# power_supply.net
KiCad netlist of a schematic drawn in EAGLE
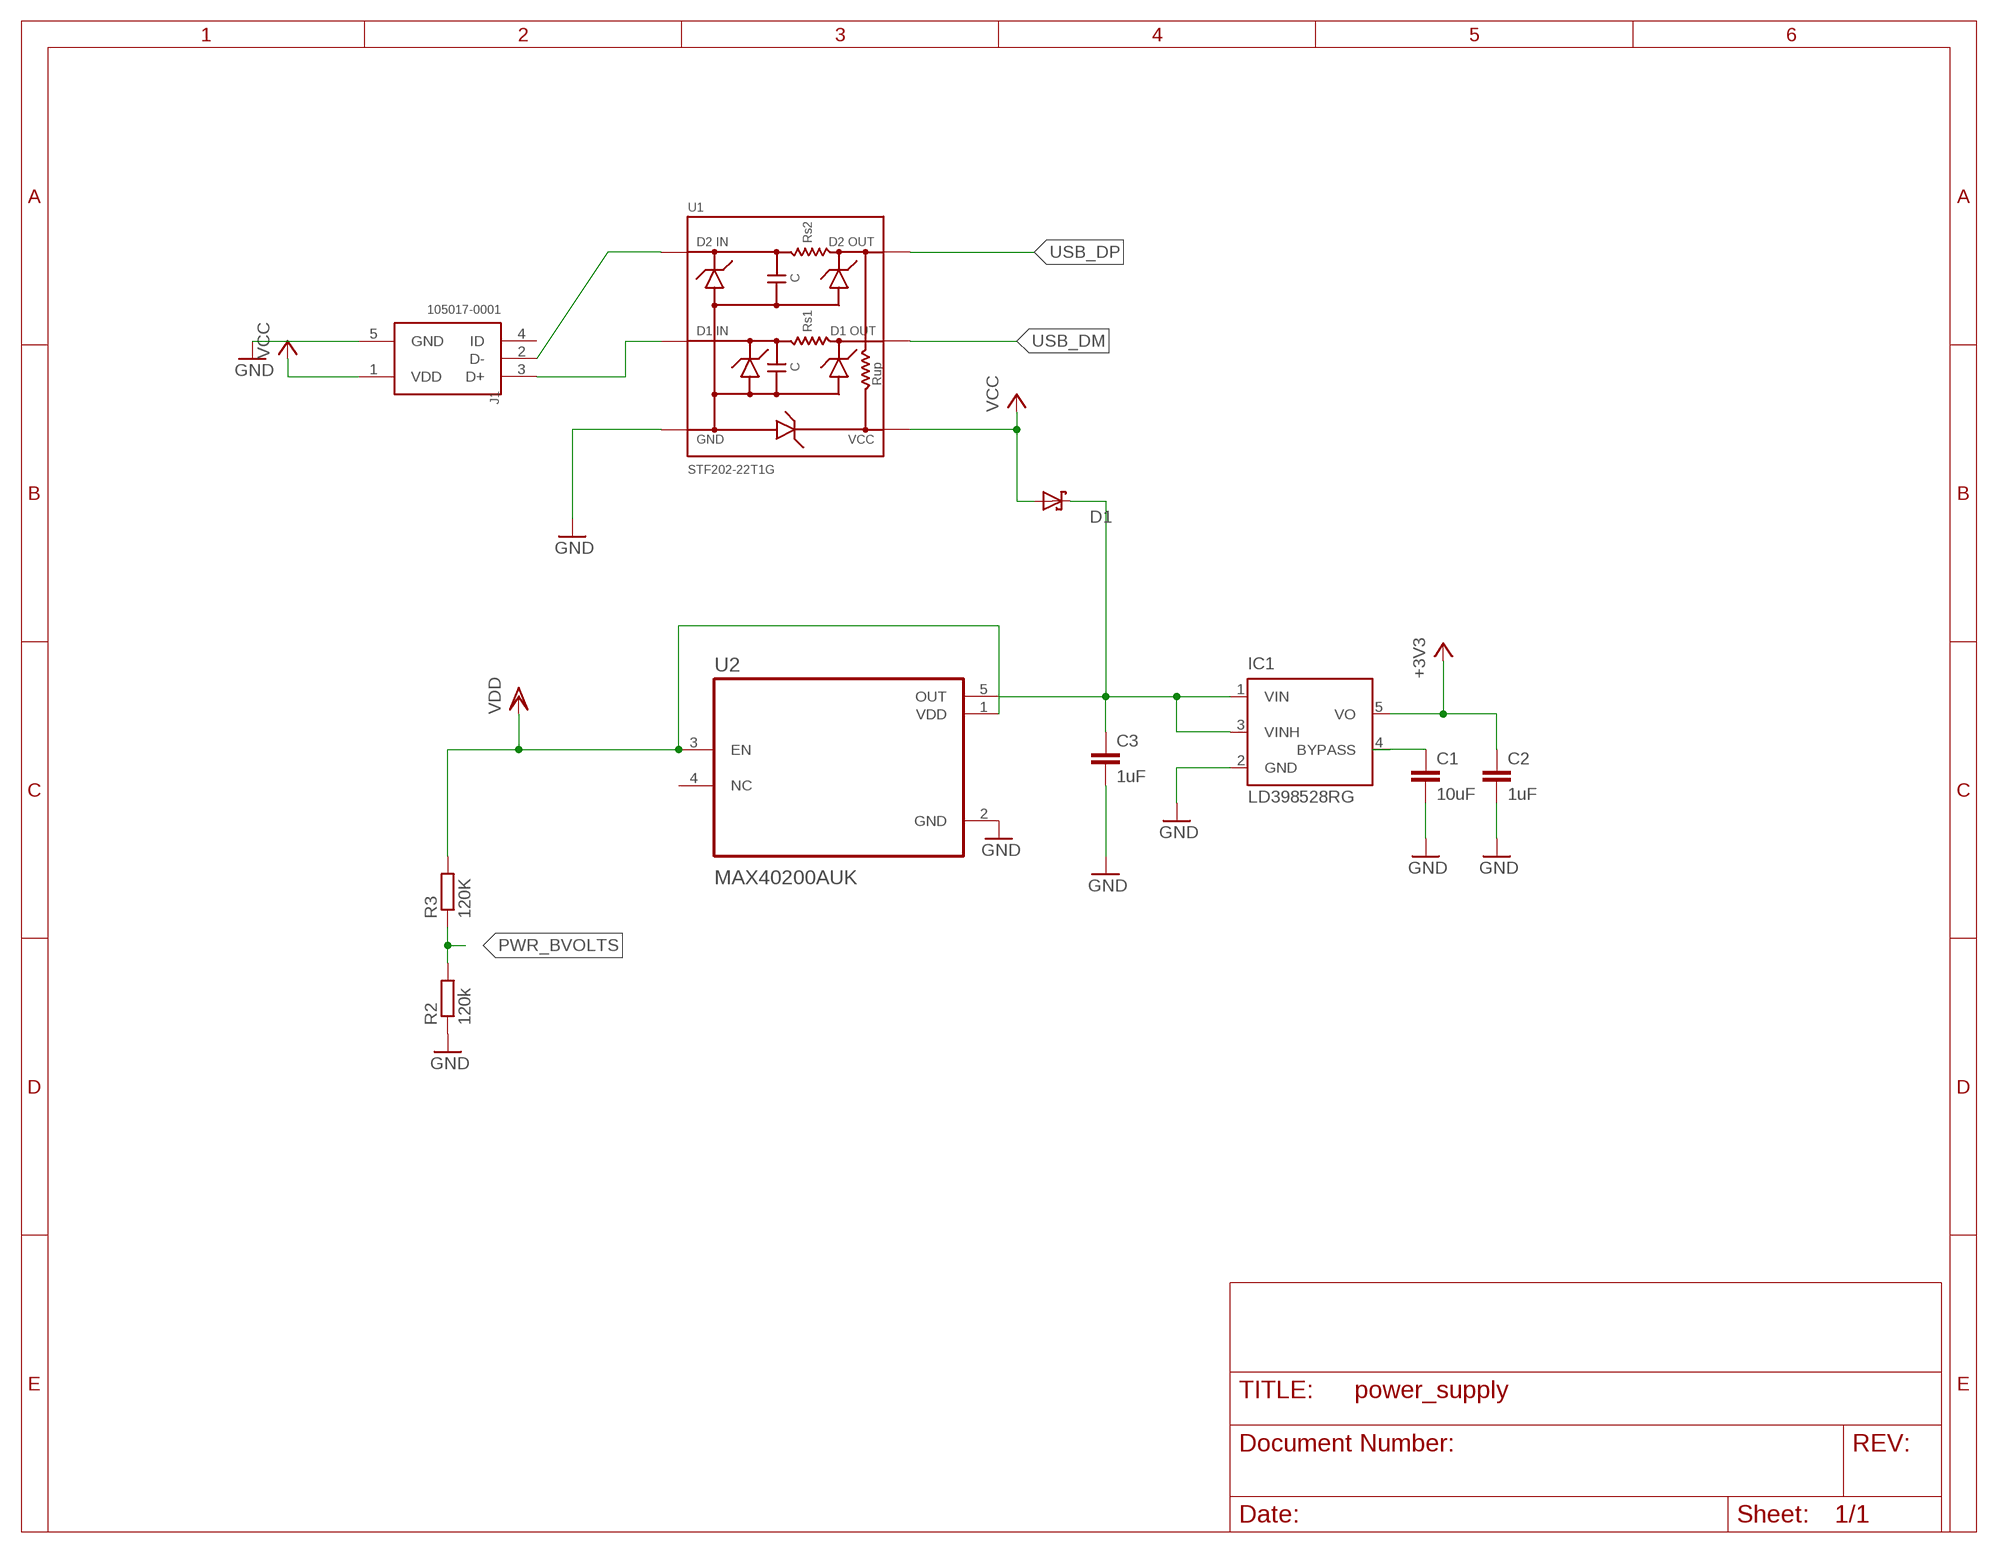
[diagram p0: schematic, sheet 1]

(export (version "E")
  (design (tool "Eeschema 10.0.6"))
  (components
    (comp (ref "C1")
      (value "10uF")
      (footprint "eagle-import:C0603")
      (libsource (lib "eagle-import") (part "C-EUC0603"))
    )
    (comp (ref "C2")
      (value "1uF")
      (footprint "eagle-import:C0603")
      (libsource (lib "eagle-import") (part "C-EUC0603"))
    )
    (comp (ref "C3")
      (value "1uF")
      (footprint "eagle-import:C0603")
      (libsource (lib "eagle-import") (part "C-EUC0603"))
    )
    (comp (ref "D1")
      (value "SCHOTTKY-DIODEDFLS130L-7")
      (footprint "eagle-import:POWERDI-123")
      (fields (field (name "MF") "Diodes Inc") (field (name "MPN") "DFLS130L-7"))
      (libsource (lib "eagle-import") (part "SCHOTTKY-DIODEDFLS130L-7"))
    )
    (comp (ref "IC1")
      (value "LD398528RG")
      (footprint "eagle-import:TSOT23-5L")
      (libsource (lib "eagle-import") (part "LD3985G28R"))
    )
    (comp (ref "J1")
      (value "105017-0001")
      (footprint "eagle-import:MOLEX_105017-0001")
      (fields (field (name "MF") "Molex"))
      (libsource (lib "eagle-import") (part "105017-0001"))
    )
    (comp (ref "R2")
      (value "120k")
      (footprint "eagle-import:R0603")
      (libsource (lib "eagle-import") (part "R-EU_R0603"))
    )
    (comp (ref "R3")
      (value "120K")
      (footprint "eagle-import:R0603")
      (libsource (lib "eagle-import") (part "R-EU_R0603"))
    )
    (comp (ref "U1")
      (value "STF202-22T1G")
      (footprint "eagle-import:STF202-22T1G")
      (fields (field (name "MF") "ON Semiconductor"))
      (libsource (lib "eagle-import") (part "STF202-22T1G"))
    )
    (comp (ref "U2")
      (value "MAX40200AUK")
      (footprint "eagle-import:21-0057F")
      (fields (field (name "MF") "Maxim Integrated"))
      (libsource (lib "eagle-import") (part "MAX40200AUK"))
    )
  )
  (nets
    (net (code "1") (name "+3V3") (class "Default")
      (node (ref "C2") (pin "1") (pinfunction "1_1") (pintype "passive"))
      (node (ref "IC1") (pin "5") (pinfunction "VO_5") (pintype "output"))
    )
    (net (code "2") (name "GND") (class "Default")
      (node (ref "C1") (pin "2") (pinfunction "2_2") (pintype "passive"))
      (node (ref "C2") (pin "2") (pinfunction "2_2") (pintype "passive"))
      (node (ref "C3") (pin "2") (pinfunction "2_2") (pintype "passive"))
      (node (ref "IC1") (pin "2") (pinfunction "GND_2") (pintype "power_in"))
      (node (ref "J1") (pin "5") (pinfunction "GND_5") (pintype "power_in"))
      (node (ref "R2") (pin "1") (pinfunction "1_1") (pintype "passive"))
      (node (ref "U1") (pin "6") (pinfunction "GND_6") (pintype "bidirectional"))
      (node (ref "U2") (pin "2") (pinfunction "GND_2") (pintype "power_in"))
    )
    (net (code "3") (name "Net-(IC1-BYPASS)") (class "Default")
      (node (ref "C1") (pin "1") (pinfunction "1_1") (pintype "passive"))
      (node (ref "IC1") (pin "4") (pinfunction "BYPASS_4") (pintype "passive"))
    )
    (net (code "4") (name "Net-(IC1-VIN)") (class "Default")
      (node (ref "C3") (pin "1") (pinfunction "1_1") (pintype "passive"))
      (node (ref "D1") (pin "C") (pinfunction "C_C") (pintype "passive"))
      (node (ref "IC1") (pin "1") (pinfunction "VIN_1") (pintype "input"))
      (node (ref "IC1") (pin "3") (pinfunction "VINH_3") (pintype "input"))
      (node (ref "U2") (pin "5") (pinfunction "OUT_5") (pintype "power_in"))
    )
    (net (code "5") (name "Net-(J1-D-)") (class "Default")
      (node (ref "J1") (pin "2") (pinfunction "D-_2") (pintype "bidirectional"))
      (node (ref "U1") (pin "4") (pinfunction "D2-OUT_4") (pintype "bidirectional"))
    )
    (net (code "6") (name "PWR_BVOLTS") (class "Default")
      (node (ref "R2") (pin "2") (pinfunction "2_2") (pintype "passive"))
      (node (ref "R3") (pin "1") (pinfunction "1_1") (pintype "passive"))
    )
    (net (code "7") (name "USB_DM") (class "Default")
      (node (ref "U1") (pin "2") (pinfunction "D1-IN_2") (pintype "bidirectional"))
    )
    (net (code "8") (name "USB_DP") (class "Default")
      (node (ref "J1") (pin "3") (pinfunction "D+_3") (pintype "bidirectional"))
      (node (ref "U1") (pin "3") (pinfunction "D2-IN_3") (pintype "bidirectional"))
      (node (ref "U1") (pin "5") (pinfunction "D1-OUT_5") (pintype "bidirectional"))
    )
    (net (code "9") (name "VCC") (class "Default")
      (node (ref "D1") (pin "A") (pinfunction "A_A") (pintype "passive"))
      (node (ref "J1") (pin "1") (pinfunction "VDD_1") (pintype "power_in"))
      (node (ref "U1") (pin "1") (pinfunction "VCC_1") (pintype "bidirectional"))
    )
    (net (code "10") (name "VDD") (class "Default")
      (node (ref "R3") (pin "2") (pinfunction "2_2") (pintype "passive"))
      (node (ref "U2") (pin "1") (pinfunction "VDD_1") (pintype "power_in"))
      (node (ref "U2") (pin "3") (pinfunction "EN_3") (pintype "input"))
    )
    (net (code "11") (name "unconnected-(J1-ID-Pad4)") (class "Default")
      (node (ref "J1") (pin "4") (pinfunction "ID_4") (pintype "passive"))
    )
    (net (code "12") (name "unconnected-(U2-NC-Pad4)") (class "Default")
      (node (ref "U2") (pin "4") (pinfunction "NC_4") (pintype "bidirectional"))
    )
  )
)
